# I2C.net
KiCad netlist of a schematic drawn in Altium Designer
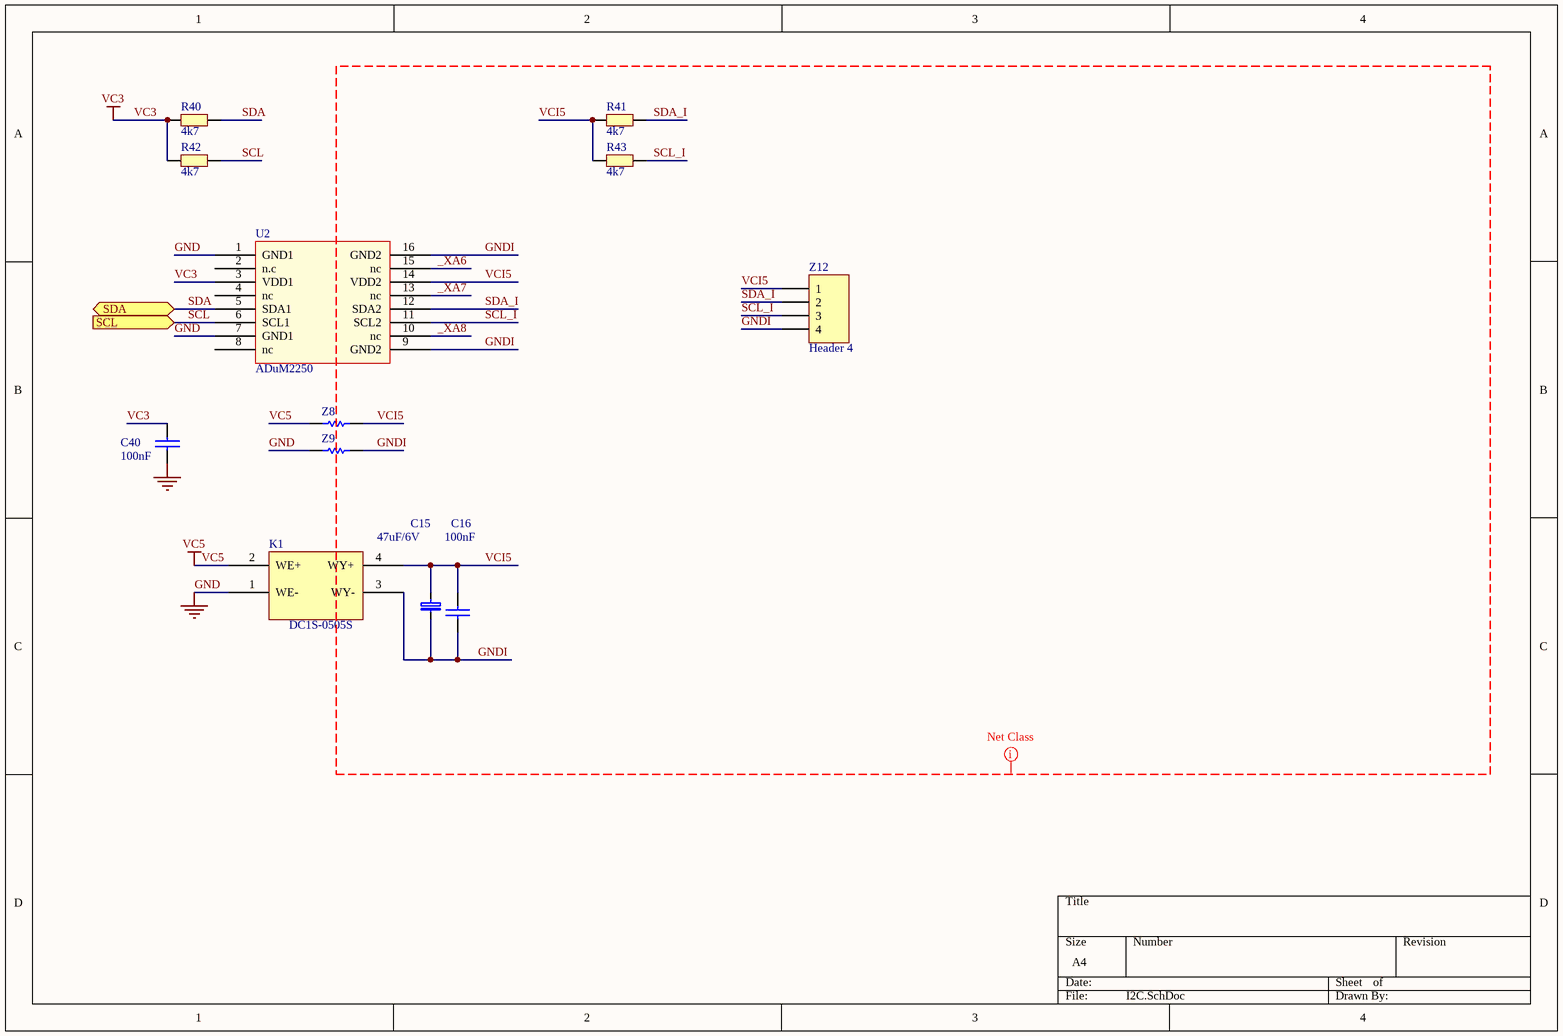
[diagram p0: I2C.SchDoc]

(export (version "E")
  (design (tool "Eeschema 10.0.6"))
  (components
    (comp (ref "C15")
      (value "47uF/6V")
      (footprint "CAP_C")
      (description "KONDENSATOR ELEKTROLITYCZNY TANTALOWY SMD")
      (libsource (lib "*") (part "CAP_TANTAL_SMD"))
    )
    (comp (ref "C16") (value "100nF") (footprint "0805C") (libsource (lib "*") (part "ProE70.tmp_100n_4")))
    (comp (ref "C40") (value "100nF") (footprint "0805C") (libsource (lib "*") (part "ProE70.tmp_100n_4")))
    (comp (ref "K1")
      (value "DC1S-0505S")
      (footprint "DCDC_SIL4")
      (libsource (lib "ElhosSchLib") (part "DCDC_AM1S"))
    )
    (comp (ref "R40") (value "4k7") (footprint "0805R") (libsource (lib "*") (part "RES3")))
    (comp (ref "R41") (value "4k7") (footprint "0805R") (libsource (lib "*") (part "RES3")))
    (comp (ref "R42") (value "4k7") (footprint "0805R") (libsource (lib "*") (part "RES3")))
    (comp (ref "R43") (value "4k7") (footprint "0805R") (libsource (lib "*") (part "RES3")))
    (comp (ref "U2")
      (value "ADuM2250")
      (footprint "SMD16B")
      (libsource (lib "ElhosSchLib") (part "ADuM2250"))
    )
    (comp (ref "Z8")
      (value "0R")
      (footprint "1206R")
      (description "Semiconductor Resistor")
      (fields (field (name "PUBLISHER") "Altium Limited"))
      (libsource (lib "Miscellaneous Devices") (part "Res Semi"))
    )
    (comp (ref "Z9")
      (value "0R")
      (footprint "1206R")
      (description "Semiconductor Resistor")
      (fields (field (name "PUBLISHER") "Altium Limited"))
      (libsource (lib "Miscellaneous Devices") (part "Res Semi"))
    )
    (comp (ref "Z12")
      (value "Header 4")
      (footprint "ARC-L-4-3.5")
      (description "Header, 4-Pin")
      (fields (field (name "PUBLISHER") "Altium Limited"))
      (libsource (lib "Miscellaneous Connectors") (part "Header 4"))
    )
  )
  (nets
    (net (code "1") (name "/GNDI") (class "Default")
      (node (ref "C15") (pin "1") (pintype "passive"))
      (node (ref "C16") (pin "1") (pintype "passive"))
      (node (ref "K1") (pin "3") (pinfunction "WY-_3") (pintype "passive"))
      (node (ref "U2") (pin "16") (pinfunction "GND2_16") (pintype "passive"))
      (node (ref "U2") (pin "9") (pinfunction "GND2_9") (pintype "passive"))
      (node (ref "Z12") (pin "4") (pinfunction "4_4") (pintype "passive"))
      (node (ref "Z9") (pin "2") (pinfunction "2_2") (pintype "passive"))
    )
    (net (code "2") (name "/SCL") (class "Default")
      (node (ref "R42") (pin "2") (pintype "passive"))
      (node (ref "U2") (pin "6") (pinfunction "SCL1_6") (pintype "passive"))
    )
    (net (code "3") (name "/SCL_I") (class "Default")
      (node (ref "R43") (pin "2") (pintype "passive"))
      (node (ref "U2") (pin "11") (pinfunction "SCL2_11") (pintype "passive"))
      (node (ref "Z12") (pin "3") (pinfunction "3_3") (pintype "passive"))
    )
    (net (code "4") (name "/SDA") (class "Default")
      (node (ref "R40") (pin "2") (pintype "passive"))
      (node (ref "U2") (pin "5") (pinfunction "SDA1_5") (pintype "passive"))
    )
    (net (code "5") (name "/SDA_I") (class "Default")
      (node (ref "R41") (pin "2") (pintype "passive"))
      (node (ref "U2") (pin "12") (pinfunction "SDA2_12") (pintype "passive"))
      (node (ref "Z12") (pin "2") (pinfunction "2_2") (pintype "passive"))
    )
    (net (code "6") (name "/VCI5") (class "Default")
      (node (ref "C15") (pin "2") (pintype "passive"))
      (node (ref "C16") (pin "2") (pintype "passive"))
      (node (ref "K1") (pin "4") (pinfunction "WY+_4") (pintype "passive"))
      (node (ref "R41") (pin "1") (pintype "passive"))
      (node (ref "R43") (pin "1") (pintype "passive"))
      (node (ref "U2") (pin "14") (pinfunction "VDD2_14") (pintype "passive"))
      (node (ref "Z12") (pin "1") (pinfunction "1_1") (pintype "passive"))
      (node (ref "Z8") (pin "2") (pinfunction "2_2") (pintype "passive"))
    )
    (net (code "7") (name "/_XA6") (class "Default")
      (node (ref "U2") (pin "15") (pinfunction "nc_15") (pintype "passive"))
    )
    (net (code "8") (name "/_XA7") (class "Default")
      (node (ref "U2") (pin "13") (pinfunction "nc_13") (pintype "passive"))
    )
    (net (code "9") (name "/_XA8") (class "Default")
      (node (ref "U2") (pin "10") (pinfunction "nc_10") (pintype "passive"))
    )
    (net (code "10") (name "GND") (class "Default")
      (node (ref "C40") (pin "1") (pintype "passive"))
      (node (ref "K1") (pin "1") (pinfunction "WE-_1") (pintype "passive"))
      (node (ref "U2") (pin "1") (pinfunction "GND1_1") (pintype "passive"))
      (node (ref "U2") (pin "7") (pinfunction "GND1_7") (pintype "passive"))
      (node (ref "Z9") (pin "1") (pinfunction "1_1") (pintype "passive"))
    )
    (net (code "11") (name "VC3") (class "Default")
      (node (ref "C40") (pin "2") (pintype "passive"))
      (node (ref "R40") (pin "1") (pintype "passive"))
      (node (ref "R42") (pin "1") (pintype "passive"))
      (node (ref "U2") (pin "3") (pinfunction "VDD1_3") (pintype "passive"))
    )
    (net (code "12") (name "VC5") (class "Default")
      (node (ref "K1") (pin "2") (pinfunction "WE+_2") (pintype "passive"))
      (node (ref "Z8") (pin "1") (pinfunction "1_1") (pintype "passive"))
    )
    (net (code "13") (name "unconnected-(U2-n.c-Pad2)") (class "Default")
      (node (ref "U2") (pin "2") (pinfunction "n.c_2") (pintype "passive"))
    )
    (net (code "14") (name "unconnected-(U2-nc-Pad4)") (class "Default")
      (node (ref "U2") (pin "4") (pinfunction "nc_4") (pintype "passive"))
    )
    (net (code "15") (name "unconnected-(U2-nc-Pad8)") (class "Default")
      (node (ref "U2") (pin "8") (pinfunction "nc_8") (pintype "passive"))
    )
  )
)
